# Universal_Receiver.net
KiCad netlist of a schematic drawn in EasyEDA Pro
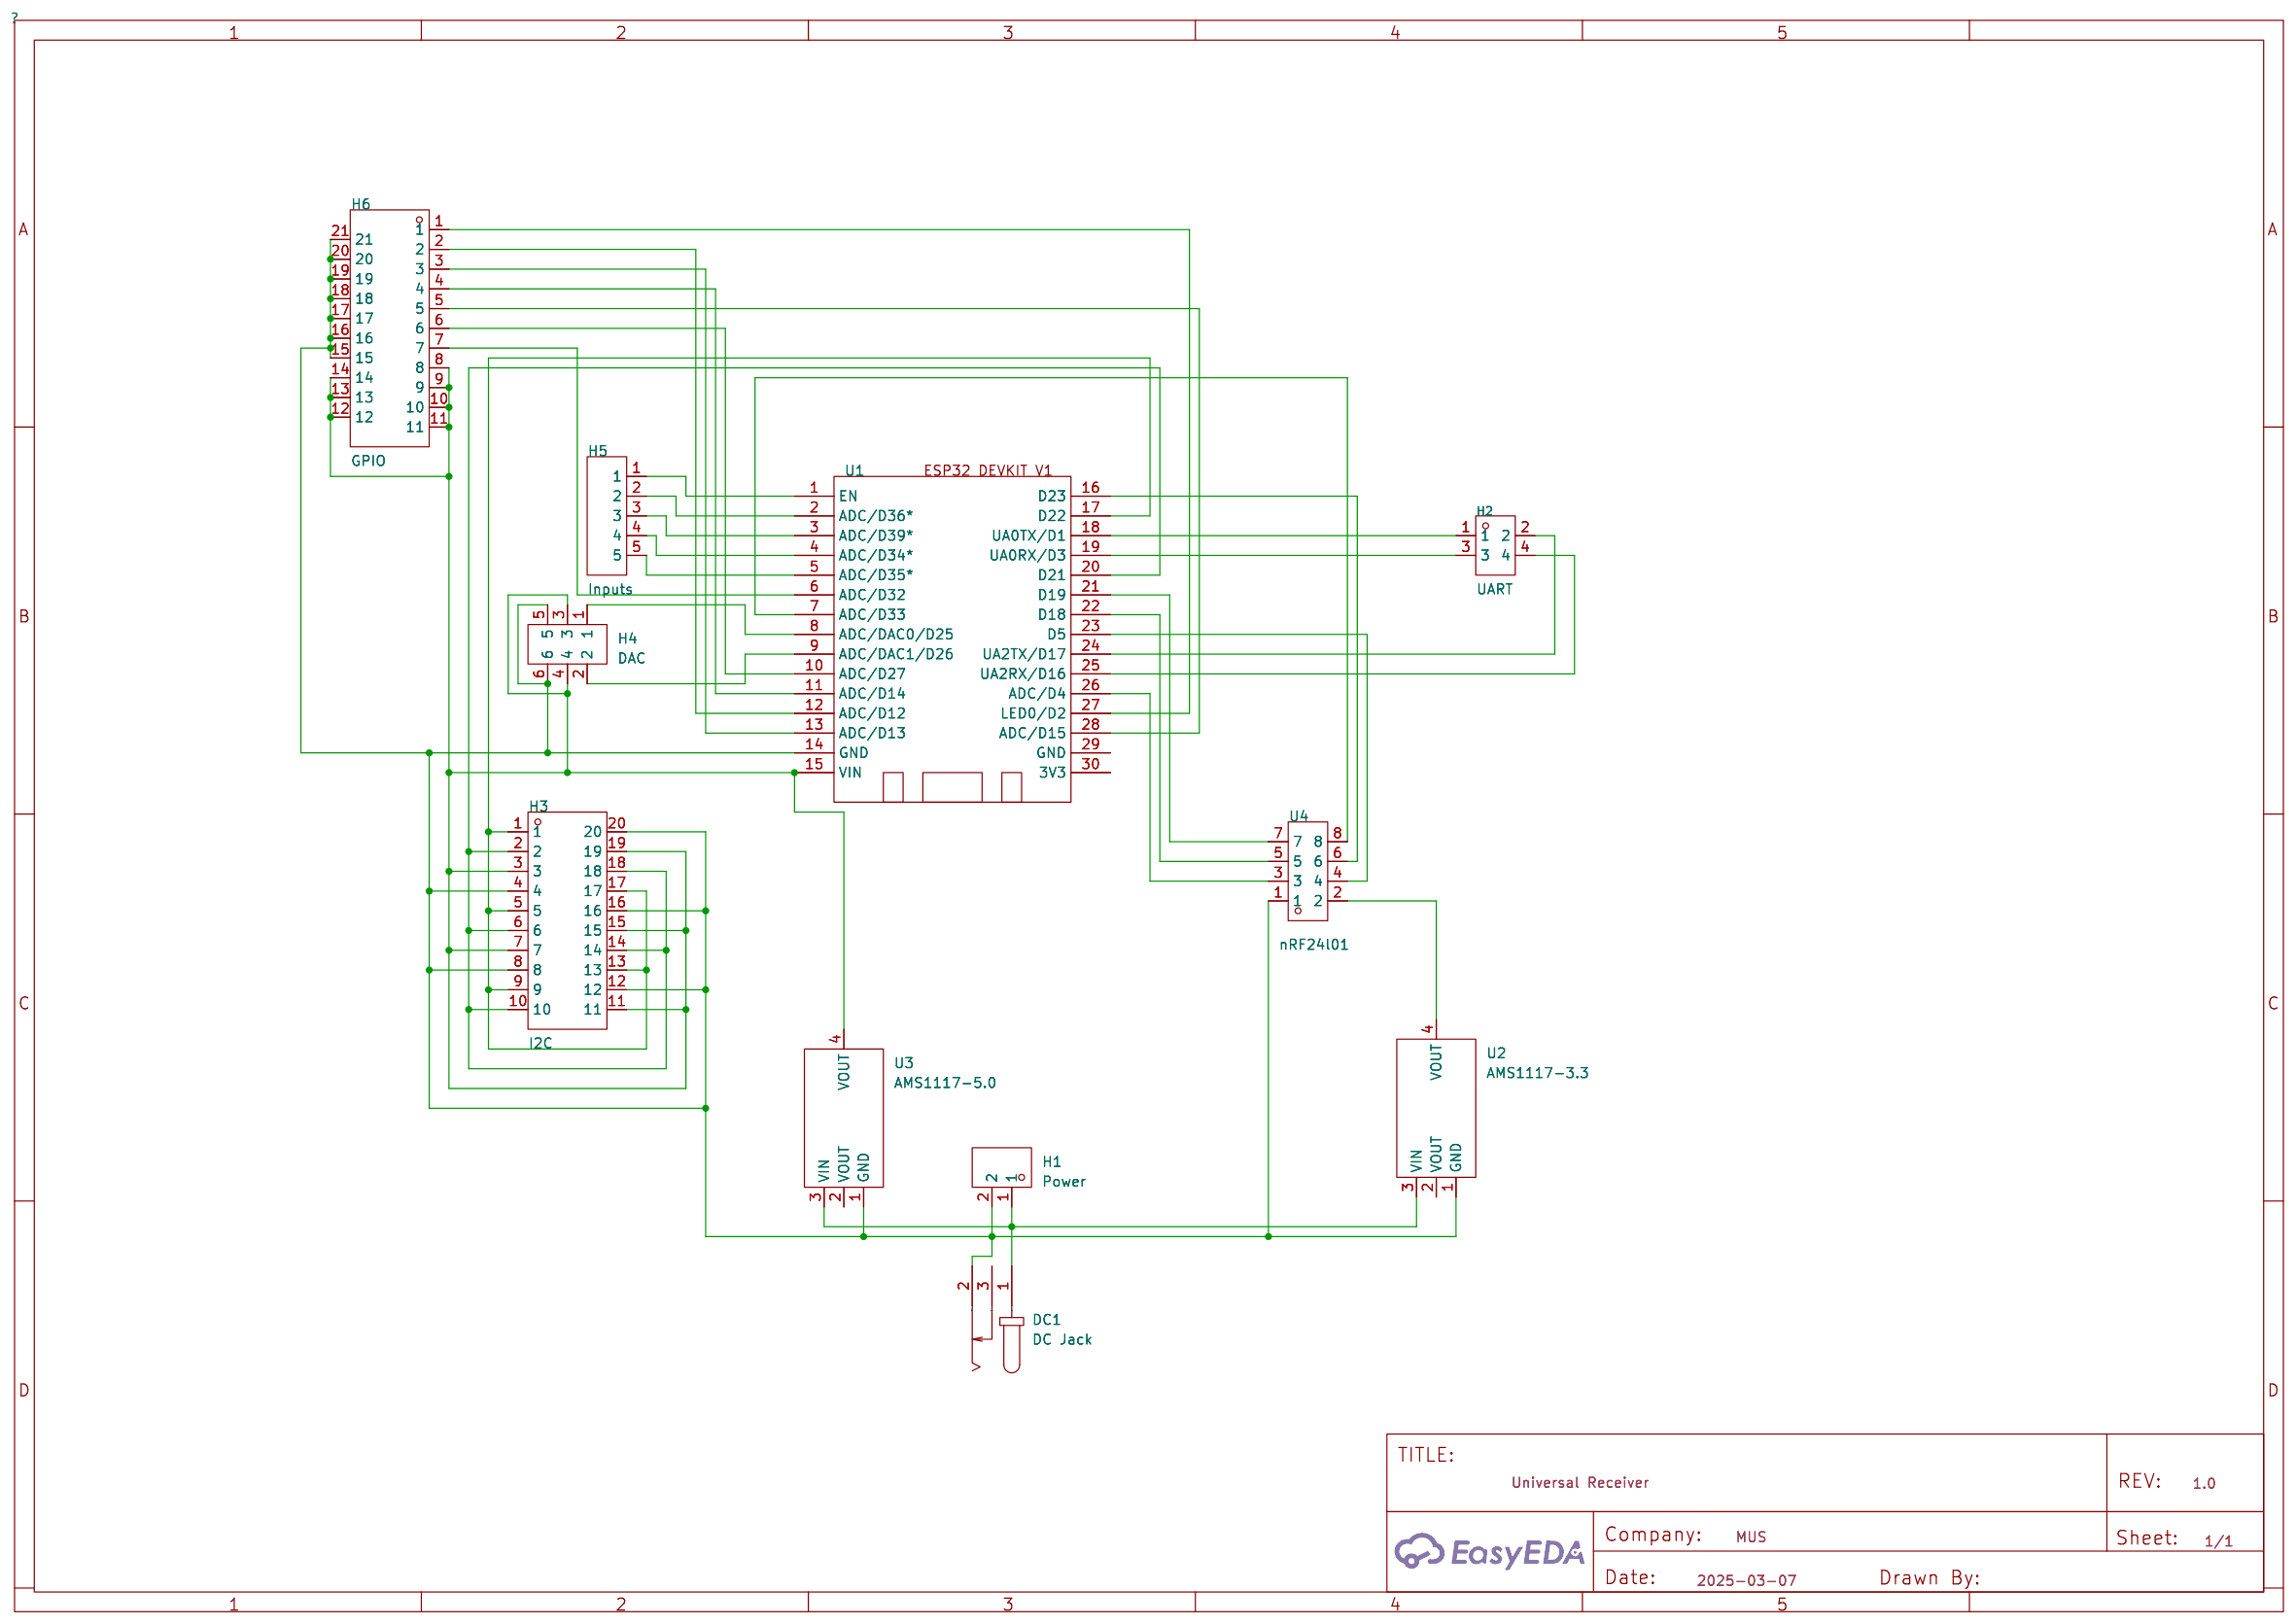
[diagram p0: schematic sheet]

(export (version "E")
  (design (tool "Eeschema 10.0.6"))
  (components
    (comp (ref "DC1")
      (value "DC Jack")
      (footprint "easyedapro:DC-IN-TH_DC-005-5A-2.0")
      (fields (field (name "Manufacturer") "XKB Connection(中国星坤)"))
      (libsource (lib "easyedapro") (part "DC-005-5A-2.0"))
    )
    (comp (ref "H1")
      (value "Power")
      (footprint "easyedapro:HDR-TH_2P-P2.54-V-M_5")
      (fields (field (name "Manufacturer") "HCTL(华灿天禄)"))
      (libsource (lib "easyedapro") (part "PZ254-1-02-Z-C"))
    )
    (comp (ref "H2")
      (value "UART")
      (footprint "easyedapro:HDR-TH_4P-P2.54-V-M-R2-C2-S2.54")
      (fields (field (name "Manufacturer") "HCTL(华灿天禄)"))
      (libsource (lib "easyedapro") (part "PZ254-2-02-Z-2.5-G1"))
    )
    (comp (ref "H3")
      (value "I2C")
      (footprint "easyedapro:HDR-TH_20P-P2.54-V-M-R4-C5-S2.54")
      (fields (field (name "Manufacturer") "hanxia(韩下)"))
      (libsource (lib "easyedapro") (part "HX PZ2.54-4X5P ZZ"))
    )
    (comp (ref "H4")
      (value "DAC")
      (footprint "easyedapro:HDR-TH_6P-P2.54-V-M-R2-C3-S2.54")
      (description "Pin Structure:2x3P Pitch:2.54mm Mounting Type:Straight Number of Rows:Double Row Number of Pins:6P")
      (fields (field (name "Manufacturer") "CONNFLY"))
      (libsource (lib "easyedapro") (part "DS1021-2X3SF11-B"))
    )
    (comp (ref "H5")
      (value "Inputs")
      (footprint "easyedapro:HDR-TH_5P-P2.54-V-M")
      (fields (field (name "Manufacturer") "XFCN(兴飞)"))
      (libsource (lib "easyedapro") (part "PZ254V-11-05P"))
    )
    (comp (ref "H6")
      (value "GPIO")
      (footprint "easyedapro:CONN-TH_HX-PZ2.54-3X7P-ZZ")
      (fields (field (name "Manufacturer") "hanxia(韩下)"))
      (libsource (lib "easyedapro") (part "HX PZ2.54-3X7P ZZ"))
    )
    (comp (ref "U1")
      (value "~")
      (footprint "easyedapro:ESP32 Devkit V1")
      (libsource (lib "easyedapro") (part "ESP32 Devkit V1"))
    )
    (comp (ref "U2")
      (value "AMS1117-3.3")
      (footprint "easyedapro:SOT-223-3_L6.5-W3.4-P2.30-LS7.0-BR")
      (fields (field (name "Manufacturer") "AMS"))
      (libsource (lib "easyedapro") (part "AMS1117-3.3"))
    )
    (comp (ref "U3")
      (value "AMS1117-5.0")
      (footprint "easyedapro:SOT-223_L6.5-W3.5-P2.30-LS7.0-BR")
      (fields (field (name "Manufacturer") "AMS"))
      (libsource (lib "easyedapro") (part "AMS1117-5.0"))
    )
    (comp (ref "U4")
      (value "nRF24l01")
      (footprint "easyedapro:HDR-TH_8P-P2.54-V-F-R2-C4-S2.54")
      (fields (field (name "Manufacturer") "ZHOURI(洲日)"))
      (libsource (lib "easyedapro") (part "2.54-2*4"))
    )
  )
  (nets
    (net (code "1") (name "Net-(U1-ADC{slash}D4)") (class "Default")
      (node (ref "U1") (pin "26") (pinfunction "ADC/D4_26") (pintype "bidirectional"))
      (node (ref "U4") (pin "3") (pinfunction "3_3") (pintype "unspecified"))
    )
    (net (code "2") (name "Net-(U1-ADC{slash}D12)") (class "Default")
      (node (ref "H6") (pin "2") (pinfunction "2_2") (pintype "unspecified"))
      (node (ref "U1") (pin "12") (pinfunction "ADC/D12_12") (pintype "bidirectional"))
    )
    (net (code "3") (name "Net-(U1-ADC{slash}D13)") (class "Default")
      (node (ref "H6") (pin "3") (pinfunction "3_3") (pintype "unspecified"))
      (node (ref "U1") (pin "13") (pinfunction "ADC/D13_13") (pintype "bidirectional"))
    )
    (net (code "4") (name "Net-(U1-ADC{slash}D14)") (class "Default")
      (node (ref "H6") (pin "4") (pinfunction "4_4") (pintype "unspecified"))
      (node (ref "U1") (pin "11") (pinfunction "ADC/D14_11") (pintype "bidirectional"))
    )
    (net (code "5") (name "Net-(U1-ADC{slash}D15)") (class "Default")
      (node (ref "H6") (pin "5") (pinfunction "5_5") (pintype "unspecified"))
      (node (ref "U1") (pin "28") (pinfunction "ADC/D15_28") (pintype "bidirectional"))
    )
    (net (code "6") (name "Net-(U1-ADC{slash}D27)") (class "Default")
      (node (ref "H6") (pin "6") (pinfunction "6_6") (pintype "unspecified"))
      (node (ref "U1") (pin "10") (pinfunction "ADC/D27_10") (pintype "bidirectional"))
    )
    (net (code "7") (name "Net-(U1-ADC{slash}D32)") (class "Default")
      (node (ref "H6") (pin "7") (pinfunction "7_7") (pintype "unspecified"))
      (node (ref "U1") (pin "6") (pinfunction "ADC/D32_6") (pintype "bidirectional"))
    )
    (net (code "8") (name "Net-(U1-ADC{slash}D33)") (class "Default")
      (node (ref "U1") (pin "7") (pinfunction "ADC/D33_7") (pintype "bidirectional"))
      (node (ref "U4") (pin "8") (pinfunction "8_8") (pintype "unspecified"))
    )
    (net (code "9") (name "Net-(U1-ADC{slash}D34*)") (class "Default")
      (node (ref "H5") (pin "4") (pinfunction "4_4") (pintype "unspecified"))
      (node (ref "U1") (pin "4") (pinfunction "ADC/D34*_4") (pintype "input"))
    )
    (net (code "10") (name "Net-(U1-ADC{slash}D35*)") (class "Default")
      (node (ref "H5") (pin "5") (pinfunction "5_5") (pintype "unspecified"))
      (node (ref "U1") (pin "5") (pinfunction "ADC/D35*_5") (pintype "input"))
    )
    (net (code "11") (name "Net-(U1-ADC{slash}D36*)") (class "Default")
      (node (ref "H5") (pin "2") (pinfunction "2_2") (pintype "unspecified"))
      (node (ref "U1") (pin "2") (pinfunction "ADC/D36*_2") (pintype "input"))
    )
    (net (code "12") (name "Net-(U1-ADC{slash}D39*)") (class "Default")
      (node (ref "H5") (pin "3") (pinfunction "3_3") (pintype "unspecified"))
      (node (ref "U1") (pin "3") (pinfunction "ADC/D39*_3") (pintype "input"))
    )
    (net (code "13") (name "Net-(U1-ADC{slash}DAC0{slash}D25)") (class "Default")
      (node (ref "H4") (pin "1") (pinfunction "1_1") (pintype "unspecified"))
      (node (ref "U1") (pin "8") (pinfunction "ADC/DAC0/D25_8") (pintype "bidirectional"))
    )
    (net (code "14") (name "Net-(U1-ADC{slash}DAC1{slash}D26)") (class "Default")
      (node (ref "H4") (pin "2") (pinfunction "2_2") (pintype "unspecified"))
      (node (ref "U1") (pin "9") (pinfunction "ADC/DAC1/D26_9") (pintype "bidirectional"))
    )
    (net (code "15") (name "Net-(U1-D5)") (class "Default")
      (node (ref "U1") (pin "23") (pinfunction "D5_23") (pintype "bidirectional"))
      (node (ref "U4") (pin "4") (pinfunction "4_4") (pintype "unspecified"))
    )
    (net (code "16") (name "Net-(U1-D18)") (class "Default")
      (node (ref "U1") (pin "22") (pinfunction "D18_22") (pintype "bidirectional"))
      (node (ref "U4") (pin "5") (pinfunction "5_5") (pintype "unspecified"))
    )
    (net (code "17") (name "Net-(U1-D19)") (class "Default")
      (node (ref "U1") (pin "21") (pinfunction "D19_21") (pintype "bidirectional"))
      (node (ref "U4") (pin "7") (pinfunction "7_7") (pintype "unspecified"))
    )
    (net (code "18") (name "Net-(U1-D21)") (class "Default")
      (node (ref "H3") (pin "10") (pinfunction "10_10") (pintype "unspecified"))
      (node (ref "H3") (pin "14") (pinfunction "14_14") (pintype "unspecified"))
      (node (ref "H3") (pin "18") (pinfunction "18_18") (pintype "unspecified"))
      (node (ref "H3") (pin "2") (pinfunction "2_2") (pintype "unspecified"))
      (node (ref "H3") (pin "6") (pinfunction "6_6") (pintype "unspecified"))
      (node (ref "U1") (pin "20") (pinfunction "D21_20") (pintype "bidirectional"))
    )
    (net (code "19") (name "Net-(U1-D22)") (class "Default")
      (node (ref "H3") (pin "1") (pinfunction "1_1") (pintype "unspecified"))
      (node (ref "H3") (pin "13") (pinfunction "13_13") (pintype "unspecified"))
      (node (ref "H3") (pin "17") (pinfunction "17_17") (pintype "unspecified"))
      (node (ref "H3") (pin "5") (pinfunction "5_5") (pintype "unspecified"))
      (node (ref "H3") (pin "9") (pinfunction "9_9") (pintype "unspecified"))
      (node (ref "U1") (pin "17") (pinfunction "D22_17") (pintype "bidirectional"))
    )
    (net (code "20") (name "Net-(U1-D23)") (class "Default")
      (node (ref "U1") (pin "16") (pinfunction "D23_16") (pintype "bidirectional"))
      (node (ref "U4") (pin "6") (pinfunction "6_6") (pintype "unspecified"))
    )
    (net (code "21") (name "Net-(U1-EN)") (class "Default")
      (node (ref "H5") (pin "1") (pinfunction "1_1") (pintype "unspecified"))
      (node (ref "U1") (pin "1") (pinfunction "EN_1") (pintype "bidirectional"))
    )
    (net (code "22") (name "Net-(U1-LED0{slash}D2)") (class "Default")
      (node (ref "H6") (pin "1") (pinfunction "1_1") (pintype "unspecified"))
      (node (ref "U1") (pin "27") (pinfunction "LED0/D2_27") (pintype "bidirectional"))
    )
    (net (code "23") (name "Net-(U1-UA0RX{slash}D3)") (class "Default")
      (node (ref "H2") (pin "3") (pinfunction "3_3") (pintype "input"))
      (node (ref "U1") (pin "19") (pinfunction "UA0RX/D3_19") (pintype "bidirectional"))
    )
    (net (code "24") (name "Net-(U1-UA0TX{slash}D1)") (class "Default")
      (node (ref "H2") (pin "1") (pinfunction "1_1") (pintype "input"))
      (node (ref "U1") (pin "18") (pinfunction "UA0TX/D1_18") (pintype "bidirectional"))
    )
    (net (code "25") (name "Net-(U1-UA2RX{slash}D16)") (class "Default")
      (node (ref "H2") (pin "4") (pinfunction "4_4") (pintype "input"))
      (node (ref "U1") (pin "25") (pinfunction "UA2RX/D16_25") (pintype "bidirectional"))
    )
    (net (code "26") (name "Net-(U1-UA2TX{slash}D17)") (class "Default")
      (node (ref "H2") (pin "2") (pinfunction "2_2") (pintype "input"))
      (node (ref "U1") (pin "24") (pinfunction "UA2TX/D17_24") (pintype "bidirectional"))
    )
    (net (code "27") (name "Net-(U1-VIN)") (class "Default")
      (node (ref "H3") (pin "11") (pinfunction "11_11") (pintype "unspecified"))
      (node (ref "H3") (pin "15") (pinfunction "15_15") (pintype "unspecified"))
      (node (ref "H3") (pin "19") (pinfunction "19_19") (pintype "unspecified"))
      (node (ref "H3") (pin "3") (pinfunction "3_3") (pintype "unspecified"))
      (node (ref "H3") (pin "7") (pinfunction "7_7") (pintype "unspecified"))
      (node (ref "H4") (pin "3") (pinfunction "3_3") (pintype "unspecified"))
      (node (ref "H4") (pin "4") (pinfunction "4_4") (pintype "unspecified"))
      (node (ref "H6") (pin "10") (pinfunction "10_10") (pintype "unspecified"))
      (node (ref "H6") (pin "11") (pinfunction "11_11") (pintype "unspecified"))
      (node (ref "H6") (pin "12") (pinfunction "12_12") (pintype "unspecified"))
      (node (ref "H6") (pin "13") (pinfunction "13_13") (pintype "unspecified"))
      (node (ref "H6") (pin "14") (pinfunction "14_14") (pintype "unspecified"))
      (node (ref "H6") (pin "8") (pinfunction "8_8") (pintype "unspecified"))
      (node (ref "H6") (pin "9") (pinfunction "9_9") (pintype "unspecified"))
      (node (ref "U1") (pin "15") (pinfunction "VIN_15") (pintype "input"))
      (node (ref "U3") (pin "4") (pinfunction "VOUT_4") (pintype "unspecified"))
    )
    (net (code "28") (name "Net-(U2-GND)") (class "Default")
      (node (ref "DC1") (pin "2") (pinfunction "2_2") (pintype "unspecified"))
      (node (ref "H1") (pin "2") (pinfunction "2_2") (pintype "unspecified"))
      (node (ref "H3") (pin "12") (pinfunction "12_12") (pintype "unspecified"))
      (node (ref "H3") (pin "16") (pinfunction "16_16") (pintype "unspecified"))
      (node (ref "H3") (pin "20") (pinfunction "20_20") (pintype "unspecified"))
      (node (ref "H3") (pin "4") (pinfunction "4_4") (pintype "unspecified"))
      (node (ref "H3") (pin "8") (pinfunction "8_8") (pintype "unspecified"))
      (node (ref "H4") (pin "5") (pinfunction "5_5") (pintype "unspecified"))
      (node (ref "H4") (pin "6") (pinfunction "6_6") (pintype "unspecified"))
      (node (ref "H6") (pin "15") (pinfunction "15_15") (pintype "unspecified"))
      (node (ref "H6") (pin "16") (pinfunction "16_16") (pintype "unspecified"))
      (node (ref "H6") (pin "17") (pinfunction "17_17") (pintype "unspecified"))
      (node (ref "H6") (pin "18") (pinfunction "18_18") (pintype "unspecified"))
      (node (ref "H6") (pin "19") (pinfunction "19_19") (pintype "unspecified"))
      (node (ref "H6") (pin "20") (pinfunction "20_20") (pintype "unspecified"))
      (node (ref "H6") (pin "21") (pinfunction "21_21") (pintype "unspecified"))
      (node (ref "U1") (pin "14") (pinfunction "GND_14") (pintype "bidirectional"))
      (node (ref "U2") (pin "1") (pinfunction "GND_1") (pintype "unspecified"))
      (node (ref "U3") (pin "1") (pinfunction "GND_1") (pintype "unspecified"))
      (node (ref "U4") (pin "1") (pinfunction "1_1") (pintype "unspecified"))
    )
    (net (code "29") (name "Net-(U2-VIN)") (class "Default")
      (node (ref "DC1") (pin "1") (pinfunction "1_1") (pintype "unspecified"))
      (node (ref "H1") (pin "1") (pinfunction "1_1") (pintype "unspecified"))
      (node (ref "U2") (pin "3") (pinfunction "VIN_3") (pintype "unspecified"))
      (node (ref "U3") (pin "3") (pinfunction "VIN_3") (pintype "unspecified"))
    )
    (net (code "30") (name "Net-(U2-VOUT-Pad4)") (class "Default")
      (node (ref "U2") (pin "4") (pinfunction "VOUT_4") (pintype "unspecified"))
      (node (ref "U4") (pin "2") (pinfunction "2_2") (pintype "unspecified"))
    )
    (net (code "31") (name "unconnected-(DC1-Pad3)") (class "Default")
      (node (ref "DC1") (pin "3") (pinfunction "3_3") (pintype "unspecified"))
    )
    (net (code "32") (name "unconnected-(U1-3V3-Pad30)") (class "Default")
      (node (ref "U1") (pin "30") (pinfunction "3V3_30") (pintype "bidirectional"))
    )
    (net (code "33") (name "unconnected-(U1-GND-Pad29)") (class "Default")
      (node (ref "U1") (pin "29") (pinfunction "GND_29") (pintype "bidirectional"))
    )
    (net (code "34") (name "unconnected-(U2-VOUT-Pad2)") (class "Default")
      (node (ref "U2") (pin "2") (pinfunction "VOUT_2") (pintype "unspecified"))
    )
    (net (code "35") (name "unconnected-(U3-VOUT-Pad2)") (class "Default")
      (node (ref "U3") (pin "2") (pinfunction "VOUT_2") (pintype "unspecified"))
    )
  )
)
